# Ramps_Driver_LED_Tester.net
KiCad netlist of a schematic drawn in EAGLE
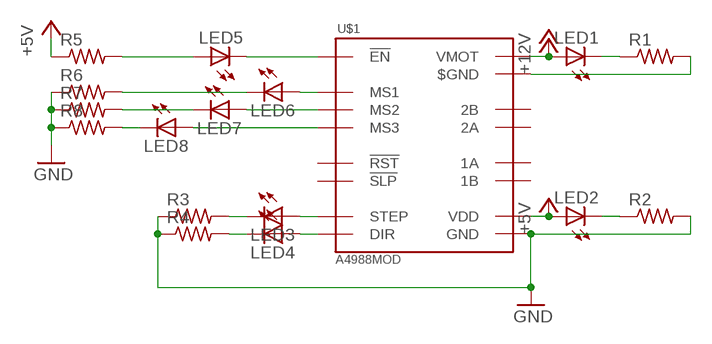
[diagram p0: schematic, sheet 1]

(export (version "E")
  (design (tool "Eeschema 10.0.6"))
  (components
    (comp (ref "LED1")
      (value "LEDCHIPLED_0805")
      (footprint "eagle-import:CHIPLED_0805")
      (libsource (lib "eagle-import") (part "LEDCHIPLED_0805"))
    )
    (comp (ref "LED2")
      (value "LEDCHIPLED_0805")
      (footprint "eagle-import:CHIPLED_0805")
      (libsource (lib "eagle-import") (part "LEDCHIPLED_0805"))
    )
    (comp (ref "LED3")
      (value "LEDCHIPLED_0805")
      (footprint "eagle-import:CHIPLED_0805")
      (libsource (lib "eagle-import") (part "LEDCHIPLED_0805"))
    )
    (comp (ref "LED4")
      (value "LEDCHIPLED_0805")
      (footprint "eagle-import:CHIPLED_0805")
      (libsource (lib "eagle-import") (part "LEDCHIPLED_0805"))
    )
    (comp (ref "LED5")
      (value "LEDCHIPLED_0805")
      (footprint "eagle-import:CHIPLED_0805")
      (libsource (lib "eagle-import") (part "LEDCHIPLED_0805"))
    )
    (comp (ref "LED6")
      (value "LEDCHIPLED_0805")
      (footprint "eagle-import:CHIPLED_0805")
      (libsource (lib "eagle-import") (part "LEDCHIPLED_0805"))
    )
    (comp (ref "LED7")
      (value "LEDCHIPLED_0805")
      (footprint "eagle-import:CHIPLED_0805")
      (libsource (lib "eagle-import") (part "LEDCHIPLED_0805"))
    )
    (comp (ref "LED8")
      (value "LEDCHIPLED_0805")
      (footprint "eagle-import:CHIPLED_0805")
      (libsource (lib "eagle-import") (part "LEDCHIPLED_0805"))
    )
    (comp (ref "R1")
      (value "R-US_R0805")
      (footprint "eagle-import:R0805")
      (libsource (lib "eagle-import") (part "R-US_R0805"))
    )
    (comp (ref "R2")
      (value "R-US_R0805")
      (footprint "eagle-import:R0805")
      (libsource (lib "eagle-import") (part "R-US_R0805"))
    )
    (comp (ref "R3")
      (value "R-US_R0805")
      (footprint "eagle-import:R0805")
      (libsource (lib "eagle-import") (part "R-US_R0805"))
    )
    (comp (ref "R4")
      (value "R-US_R0805")
      (footprint "eagle-import:R0805")
      (libsource (lib "eagle-import") (part "R-US_R0805"))
    )
    (comp (ref "R5")
      (value "R-US_R0805")
      (footprint "eagle-import:R0805")
      (libsource (lib "eagle-import") (part "R-US_R0805"))
    )
    (comp (ref "R6")
      (value "R-US_R0805")
      (footprint "eagle-import:R0805")
      (libsource (lib "eagle-import") (part "R-US_R0805"))
    )
    (comp (ref "R7")
      (value "R-US_R0805")
      (footprint "eagle-import:R0805")
      (libsource (lib "eagle-import") (part "R-US_R0805"))
    )
    (comp (ref "R8")
      (value "R-US_R0805")
      (footprint "eagle-import:R0805")
      (libsource (lib "eagle-import") (part "R-US_R0805"))
    )
    (comp (ref "U$1")
      (value "A4988MOD")
      (footprint "eagle-import:A4988MOD")
      (libsource (lib "eagle-import") (part "A4988MOD"))
    )
  )
  (nets
    (net (code "1") (name "+5V") (class "Default")
      (node (ref "LED2") (pin "A") (pinfunction "A_A") (pintype "passive"))
      (node (ref "R5") (pin "1") (pinfunction "1_1") (pintype "passive"))
      (node (ref "U$1") (pin "P$10") (pinfunction "VDD_P$10") (pintype "bidirectional"))
    )
    (net (code "2") (name "+12V") (class "Default")
      (node (ref "LED1") (pin "A") (pinfunction "A_A") (pintype "passive"))
      (node (ref "U$1") (pin "P$16") (pinfunction "VMOT_P$16") (pintype "bidirectional"))
    )
    (net (code "3") (name "GND") (class "Default")
      (node (ref "R2") (pin "2") (pinfunction "2_2") (pintype "passive"))
      (node (ref "R3") (pin "1") (pinfunction "1_1") (pintype "passive"))
      (node (ref "R4") (pin "1") (pinfunction "1_1") (pintype "passive"))
      (node (ref "R6") (pin "1") (pinfunction "1_1") (pintype "passive"))
      (node (ref "R7") (pin "1") (pinfunction "1_1") (pintype "passive"))
      (node (ref "R8") (pin "1") (pinfunction "1_1") (pintype "passive"))
      (node (ref "U$1") (pin "P$9") (pinfunction "GND_P$9") (pintype "bidirectional"))
    )
    (net (code "4") (name "Net-(LED1-PadC)") (class "Default")
      (node (ref "LED1") (pin "C") (pinfunction "C_C") (pintype "passive"))
      (node (ref "R1") (pin "1") (pinfunction "1_1") (pintype "passive"))
    )
    (net (code "5") (name "Net-(LED2-PadC)") (class "Default")
      (node (ref "LED2") (pin "C") (pinfunction "C_C") (pintype "passive"))
      (node (ref "R2") (pin "1") (pinfunction "1_1") (pintype "passive"))
    )
    (net (code "6") (name "Net-(LED3-PadC)") (class "Default")
      (node (ref "LED3") (pin "C") (pinfunction "C_C") (pintype "passive"))
      (node (ref "R3") (pin "2") (pinfunction "2_2") (pintype "passive"))
    )
    (net (code "7") (name "Net-(LED4-PadC)") (class "Default")
      (node (ref "LED4") (pin "C") (pinfunction "C_C") (pintype "passive"))
      (node (ref "R4") (pin "2") (pinfunction "2_2") (pintype "passive"))
    )
    (net (code "8") (name "Net-(LED5-PadA)") (class "Default")
      (node (ref "LED5") (pin "A") (pinfunction "A_A") (pintype "passive"))
      (node (ref "R5") (pin "2") (pinfunction "2_2") (pintype "passive"))
    )
    (net (code "9") (name "Net-(LED6-PadC)") (class "Default")
      (node (ref "LED6") (pin "C") (pinfunction "C_C") (pintype "passive"))
      (node (ref "R6") (pin "2") (pinfunction "2_2") (pintype "passive"))
    )
    (net (code "10") (name "Net-(LED7-PadC)") (class "Default")
      (node (ref "LED7") (pin "C") (pinfunction "C_C") (pintype "passive"))
      (node (ref "R7") (pin "2") (pinfunction "2_2") (pintype "passive"))
    )
    (net (code "11") (name "Net-(LED8-PadC)") (class "Default")
      (node (ref "LED8") (pin "C") (pinfunction "C_C") (pintype "passive"))
      (node (ref "R8") (pin "2") (pinfunction "2_2") (pintype "passive"))
    )
    (net (code "12") (name "Net-(U$1-$GND)") (class "Default")
      (node (ref "R1") (pin "2") (pinfunction "2_2") (pintype "passive"))
      (node (ref "U$1") (pin "P$15") (pinfunction "$GND_P$15") (pintype "bidirectional"))
    )
    (net (code "13") (name "Net-(U$1-DIR)") (class "Default")
      (node (ref "LED4") (pin "A") (pinfunction "A_A") (pintype "passive"))
      (node (ref "U$1") (pin "P$8") (pinfunction "DIR_P$8") (pintype "bidirectional"))
    )
    (net (code "14") (name "Net-(U$1-MS1)") (class "Default")
      (node (ref "LED6") (pin "A") (pinfunction "A_A") (pintype "passive"))
      (node (ref "U$1") (pin "P$2") (pinfunction "MS1_P$2") (pintype "bidirectional"))
    )
    (net (code "15") (name "Net-(U$1-MS2)") (class "Default")
      (node (ref "LED7") (pin "A") (pinfunction "A_A") (pintype "passive"))
      (node (ref "U$1") (pin "P$3") (pinfunction "MS2_P$3") (pintype "bidirectional"))
    )
    (net (code "16") (name "Net-(U$1-MS3)") (class "Default")
      (node (ref "LED8") (pin "A") (pinfunction "A_A") (pintype "passive"))
      (node (ref "U$1") (pin "P$4") (pinfunction "MS3_P$4") (pintype "bidirectional"))
    )
    (net (code "17") (name "Net-(U$1-STEP)") (class "Default")
      (node (ref "LED3") (pin "A") (pinfunction "A_A") (pintype "passive"))
      (node (ref "U$1") (pin "P$7") (pinfunction "STEP_P$7") (pintype "bidirectional"))
    )
    (net (code "18") (name "Net-(U$1-~{EN})") (class "Default")
      (node (ref "LED5") (pin "C") (pinfunction "C_C") (pintype "passive"))
      (node (ref "U$1") (pin "P$1") (pinfunction "~{EN}_P$1") (pintype "bidirectional"))
    )
    (net (code "19") (name "unconnected-(U$1-1A-PadP$12)") (class "Default")
      (node (ref "U$1") (pin "P$12") (pinfunction "1A_P$12") (pintype "bidirectional"))
    )
    (net (code "20") (name "unconnected-(U$1-1B-PadP$11)") (class "Default")
      (node (ref "U$1") (pin "P$11") (pinfunction "1B_P$11") (pintype "bidirectional"))
    )
    (net (code "21") (name "unconnected-(U$1-2A-PadP$13)") (class "Default")
      (node (ref "U$1") (pin "P$13") (pinfunction "2A_P$13") (pintype "bidirectional"))
    )
    (net (code "22") (name "unconnected-(U$1-2B-PadP$14)") (class "Default")
      (node (ref "U$1") (pin "P$14") (pinfunction "2B_P$14") (pintype "bidirectional"))
    )
    (net (code "23") (name "unconnected-(U$1-~{RST}-PadP$5)") (class "Default")
      (node (ref "U$1") (pin "P$5") (pinfunction "~{RST}_P$5") (pintype "bidirectional"))
    )
    (net (code "24") (name "unconnected-(U$1-~{SLP}-PadP$6)") (class "Default")
      (node (ref "U$1") (pin "P$6") (pinfunction "~{SLP}_P$6") (pintype "bidirectional"))
    )
  )
)
